# Power_Board_Schematic.net
KiCad netlist of a schematic drawn in Altium Designer
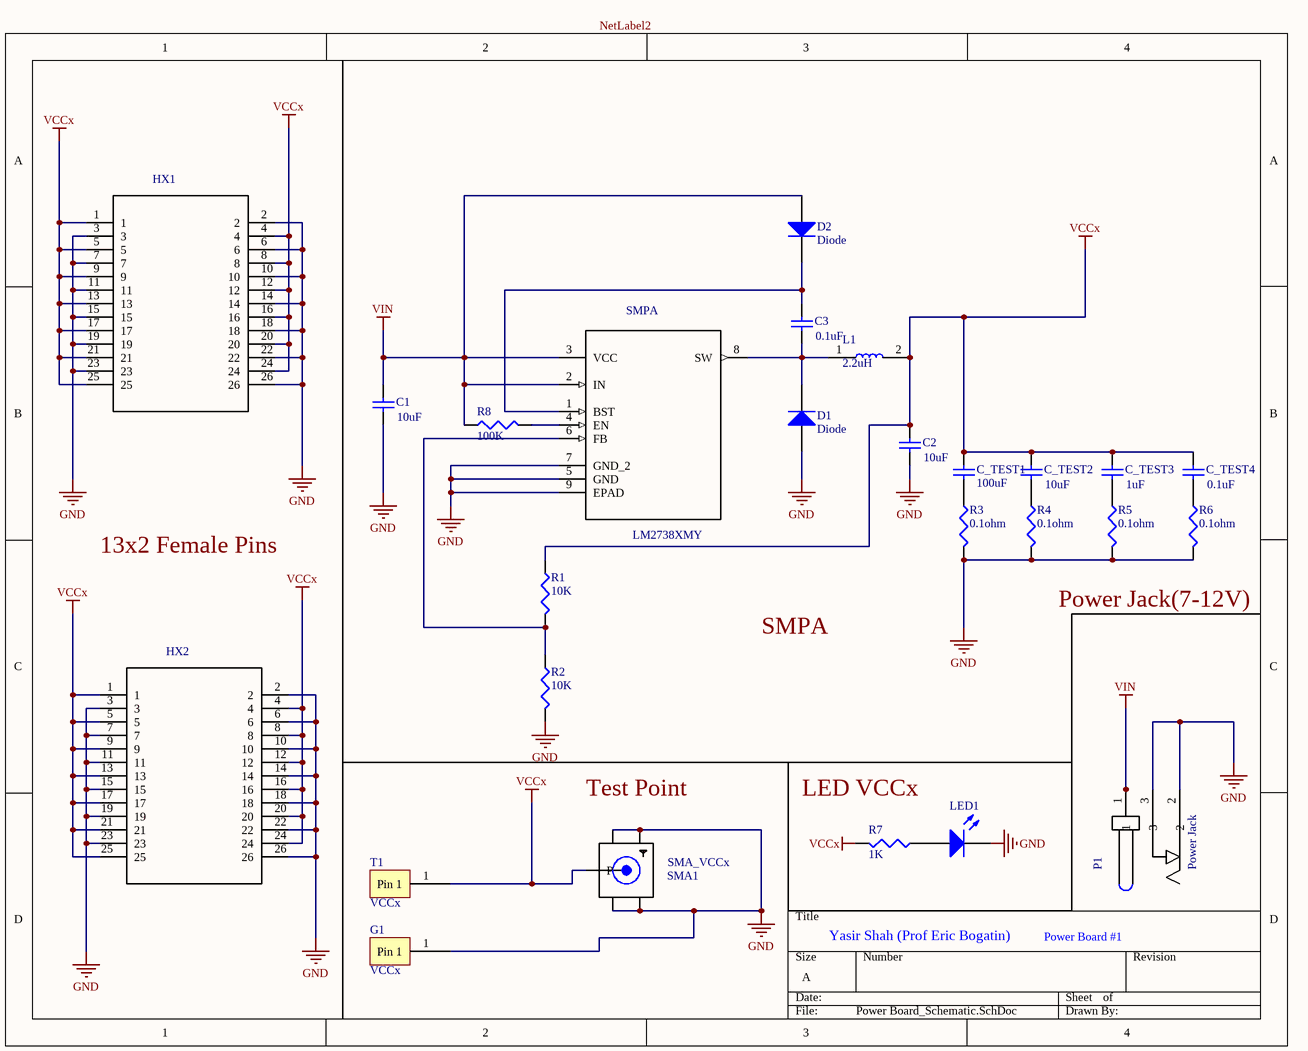
[diagram p0: Power Board_Schematic.SchDoc]

(export (version "E")
  (design (tool "Eeschema 10.0.6"))
  (components
    (comp (ref "C1")
      (value "10uF")
      (footprint "CAPC2012X140N")
      (description "Capacitor (Semiconductor SIM Model)")
      (fields (field (name "Comment") "Cap Semi") (field (name "PUBLISHER") "Altium Limited"))
      (libsource (lib "Miscellaneous Devices") (part "Cap Semi"))
    )
    (comp (ref "C2")
      (value "10uF")
      (footprint "CAPC2012X140N")
      (description "Capacitor (Semiconductor SIM Model)")
      (fields (field (name "Comment") "Cap Semi") (field (name "PUBLISHER") "Altium Limited"))
      (libsource (lib "Miscellaneous Devices") (part "Cap Semi"))
    )
    (comp (ref "C3")
      (value "0.1uF")
      (footprint "CAPC2012X140N")
      (description "Capacitor (Semiconductor SIM Model)")
      (fields (field (name "Comment") "Cap Semi") (field (name "PUBLISHER") "Altium Limited"))
      (libsource (lib "Miscellaneous Devices") (part "Cap Semi"))
    )
    (comp (ref "C_TEST1")
      (value "100uF")
      (footprint "CAPC2012X140N")
      (description "Capacitor (Semiconductor SIM Model)")
      (fields (field (name "Comment") "Cap Semi") (field (name "PUBLISHER") "Altium Limited"))
      (libsource (lib "Miscellaneous Devices") (part "Cap Semi"))
    )
    (comp (ref "C_TEST2")
      (value "10uF")
      (footprint "CAPC2012X140N")
      (description "Capacitor (Semiconductor SIM Model)")
      (fields (field (name "Comment") "Cap Semi") (field (name "PUBLISHER") "Altium Limited"))
      (libsource (lib "Miscellaneous Devices") (part "Cap Semi"))
    )
    (comp (ref "C_TEST3")
      (value "1uF")
      (footprint "CAPC2012X140N")
      (description "Capacitor (Semiconductor SIM Model)")
      (fields (field (name "Comment") "Cap Semi") (field (name "PUBLISHER") "Altium Limited"))
      (libsource (lib "Miscellaneous Devices") (part "Cap Semi"))
    )
    (comp (ref "C_TEST4")
      (value "0.1uF")
      (footprint "CAPC2012X140N")
      (description "Capacitor (Semiconductor SIM Model)")
      (fields (field (name "Comment") "Cap Semi") (field (name "PUBLISHER") "Altium Limited"))
      (libsource (lib "Miscellaneous Devices") (part "Cap Semi"))
    )
    (comp (ref "D1")
      (value "Diode")
      (footprint "D1")
      (description "Default Diode")
      (fields (field (name "PUBLISHER") "Altium Limited"))
      (libsource (lib "Miscellaneous Devices") (part "Diode"))
    )
    (comp (ref "D2")
      (value "Diode")
      (footprint "d2")
      (description "Default Diode")
      (fields (field (name "PUBLISHER") "Altium Limited"))
      (libsource (lib "Miscellaneous Devices") (part "Diode"))
    )
    (comp (ref "G1")
      (value "VCCx")
      (footprint "PCBComponent_1")
      (libsource (lib "SchematicLibrary") (part "1Pin Header"))
    )
    (comp (ref "HX1")
      (value "~")
      (footprint "TYCO_1761606-9")
      (description "Header, Pin, Idc, Amp-Latch, 26 Pos, Low Profile, Pcb, Vertical, Black")
      (fields (field (name "MF") "TE Connectivity") (field (name "MP") "1761606-9"))
      (libsource (lib "1761606-9") (part "1761606-9"))
    )
    (comp (ref "HX2")
      (value "~")
      (footprint "TYCO_1761606-9")
      (description "Header, Pin, Idc, Amp-Latch, 26 Pos, Low Profile, Pcb, Vertical, Black")
      (fields (field (name "MF") "TE Connectivity") (field (name "MP") "1761606-9"))
      (libsource (lib "1761606-9") (part "1761606-9"))
    )
    (comp (ref "L1")
      (value "2.2uH")
      (footprint "CAPC2012X140N")
      (description "Inductor Power Shielded Multi-Layer 2.2uH 20% 2MHz Ferrite 1A 195mOhm DCR 0805 Punched Paper T/R")
      (fields (field (name "MF") "TDK") (field (name "MP") "MLP2012H2R2MT0S1"))
      (libsource (lib "MLP2012H2R2MT0S1") (part "MLP2012H2R2MT0S1"))
    )
    (comp (ref "LED1")
      (value "LED2")
      (footprint "C1206")
      (description "Typical RED, GREEN, YELLOW, AMBER GaAs LED")
      (fields (field (name "PUBLISHER") "Altium Limited"))
      (libsource (lib "Miscellaneous Devices") (part "LED2"))
    )
    (comp (ref "P1")
      (value "Power Jack")
      (footprint "CUI_PJ-002AH-SMT-TR")
      (description "24 VDC 5 A Surface Mount Unshielded 2 Conductors 3 Contacts Male Power Jack")
      (fields (field (name "MF") "CUI") (field (name "MP") "PJ-002AH-SMT-TR"))
      (libsource (lib "PJ-002AH-SMT-TR") (part "PJ-002AH-SMT-TR"))
    )
    (comp (ref "R1")
      (value "10K")
      (footprint "RESC2012X70")
      (description "Resistor")
      (fields (field (name "Comment") "Res3") (field (name "PUBLISHER") "Altium Limited"))
      (libsource (lib "Miscellaneous Devices") (part "Res3"))
    )
    (comp (ref "R2")
      (value "10K")
      (footprint "RESC2012X70")
      (description "Resistor")
      (fields (field (name "Comment") "Res3") (field (name "PUBLISHER") "Altium Limited"))
      (libsource (lib "Miscellaneous Devices") (part "Res3"))
    )
    (comp (ref "R3")
      (value "0.1ohm")
      (footprint "RESC3216X65")
      (description "Resistor")
      (fields (field (name "PUBLISHER") "Altium Limited"))
      (libsource (lib "Miscellaneous Devices") (part "Res3"))
    )
    (comp (ref "R4")
      (value "0.1ohm")
      (footprint "RESC3216X65")
      (description "Resistor")
      (fields (field (name "PUBLISHER") "Altium Limited"))
      (libsource (lib "Miscellaneous Devices") (part "Res3"))
    )
    (comp (ref "R5")
      (value "0.1ohm")
      (footprint "RESC3216X65")
      (description "Resistor")
      (fields (field (name "PUBLISHER") "Altium Limited"))
      (libsource (lib "Miscellaneous Devices") (part "Res3"))
    )
    (comp (ref "R6")
      (value "0.1ohm")
      (footprint "RESC3216X65")
      (description "Resistor")
      (fields (field (name "PUBLISHER") "Altium Limited"))
      (libsource (lib "Miscellaneous Devices") (part "Res3"))
    )
    (comp (ref "R7")
      (value "1K")
      (footprint "RESC2012X70")
      (description "Resistor")
      (fields (field (name "Comment") "Res3") (field (name "PUBLISHER") "Altium Limited"))
      (libsource (lib "Miscellaneous Devices") (part "Res3"))
    )
    (comp (ref "R8")
      (value "100K")
      (footprint "RESC2012X70")
      (description "Resistor")
      (fields (field (name "Comment") "Res3") (field (name "PUBLISHER") "Altium Limited"))
      (libsource (lib "Miscellaneous Devices") (part "Res3"))
    )
    (comp (ref "SMA_VCCx")
      (value "SMA1")
      (footprint "ADAFRUIT_1865_1865(Primary)")
      (description "Edge-Launch SMA Connector for 1.6mm / 0.062 Thick PCBs")
      (fields (field (name "MP") "1865") (field (name "MF") "Keystone"))
      (libsource (lib "1865") (part "1865"))
    )
    (comp (ref "SMPA")
      (value "LM2738XMY")
      (footprint "SOP65P490X110-9N")
      (description "Swx Reg, Step d, Dc-Dc, 1.5a, 8soic")
      (fields (field (name "MF") "Texas Instruments"))
      (libsource (lib "LM2738XMY") (part "LM2738XMY"))
    )
    (comp (ref "T1")
      (value "VCCx")
      (footprint "PCBComponent_1")
      (libsource (lib "SchematicLibrary") (part "1Pin Header"))
    )
  )
  (nets
    (net (code "2") (name "GND") (class "Default")
      (node (ref "C1") (pin "1") (pinfunction "1_1") (pintype "passive"))
      (node (ref "C2") (pin "1") (pinfunction "1_1") (pintype "passive"))
      (node (ref "D1") (pin "1") (pinfunction "A_1") (pintype "passive"))
      (node (ref "G1") (pin "1") (pinfunction "Pin_1_1") (pintype "passive"))
      (node (ref "HX1") (pin "10") (pinfunction "10_10") (pintype "passive"))
      (node (ref "HX1") (pin "11") (pinfunction "11_11") (pintype "passive"))
      (node (ref "HX1") (pin "14") (pinfunction "14_14") (pintype "passive"))
      (node (ref "HX1") (pin "15") (pinfunction "15_15") (pintype "passive"))
      (node (ref "HX1") (pin "18") (pinfunction "18_18") (pintype "passive"))
      (node (ref "HX1") (pin "19") (pinfunction "19_19") (pintype "passive"))
      (node (ref "HX1") (pin "2") (pinfunction "2_2") (pintype "passive"))
      (node (ref "HX1") (pin "22") (pinfunction "22_22") (pintype "passive"))
      (node (ref "HX1") (pin "23") (pinfunction "23_23") (pintype "passive"))
      (node (ref "HX1") (pin "26") (pinfunction "26_26") (pintype "passive"))
      (node (ref "HX1") (pin "3") (pinfunction "3_3") (pintype "passive"))
      (node (ref "HX1") (pin "6") (pinfunction "6_6") (pintype "passive"))
      (node (ref "HX1") (pin "7") (pinfunction "7_7") (pintype "passive"))
      (node (ref "HX2") (pin "10") (pinfunction "10_10") (pintype "passive"))
      (node (ref "HX2") (pin "11") (pinfunction "11_11") (pintype "passive"))
      (node (ref "HX2") (pin "14") (pinfunction "14_14") (pintype "passive"))
      (node (ref "HX2") (pin "15") (pinfunction "15_15") (pintype "passive"))
      (node (ref "HX2") (pin "18") (pinfunction "18_18") (pintype "passive"))
      (node (ref "HX2") (pin "19") (pinfunction "19_19") (pintype "passive"))
      (node (ref "HX2") (pin "2") (pinfunction "2_2") (pintype "passive"))
      (node (ref "HX2") (pin "22") (pinfunction "22_22") (pintype "passive"))
      (node (ref "HX2") (pin "23") (pinfunction "23_23") (pintype "passive"))
      (node (ref "HX2") (pin "26") (pinfunction "26_26") (pintype "passive"))
      (node (ref "HX2") (pin "3") (pinfunction "3_3") (pintype "passive"))
      (node (ref "HX2") (pin "6") (pinfunction "6_6") (pintype "passive"))
      (node (ref "HX2") (pin "7") (pinfunction "7_7") (pintype "passive"))
      (node (ref "LED1") (pin "2") (pinfunction "K_2") (pintype "passive"))
      (node (ref "P1") (pin "2") (pinfunction "2_2") (pintype "passive"))
      (node (ref "P1") (pin "3") (pinfunction "3_3") (pintype "passive"))
      (node (ref "R2") (pin "2") (pinfunction "2_2") (pintype "passive"))
      (node (ref "R3") (pin "2") (pinfunction "2_2") (pintype "passive"))
      (node (ref "R4") (pin "2") (pinfunction "2_2") (pintype "passive"))
      (node (ref "R5") (pin "2") (pinfunction "2_2") (pintype "passive"))
      (node (ref "R6") (pin "2") (pinfunction "2_2") (pintype "passive"))
      (node (ref "SMA_VCCx") (pin "GND1") (pinfunction "GND1_GND1") (pintype "power_in"))
      (node (ref "SMA_VCCx") (pin "GND2") (pinfunction "GND2_GND2") (pintype "power_in"))
      (node (ref "SMA_VCCx") (pin "GND3") (pinfunction "GND3_GND3") (pintype "power_in"))
      (node (ref "SMA_VCCx") (pin "GND4") (pinfunction "GND4_GND4") (pintype "power_in"))
      (node (ref "SMPA") (pin "5") (pinfunction "GND_5") (pintype "passive"))
      (node (ref "SMPA") (pin "7") (pinfunction "GND_2_7") (pintype "passive"))
      (node (ref "SMPA") (pin "9") (pinfunction "EPAD_9") (pintype "passive"))
    )
    (net (code "3") (name "Net-(C_TEST1-Pad2)") (class "Default")
      (node (ref "C_TEST1") (pin "2") (pinfunction "2_2") (pintype "passive"))
      (node (ref "R3") (pin "1") (pinfunction "1_1") (pintype "passive"))
    )
    (net (code "4") (name "Net-(C_TEST2-Pad1)") (class "Default")
      (node (ref "C_TEST2") (pin "1") (pinfunction "1_1") (pintype "passive"))
      (node (ref "R4") (pin "1") (pinfunction "1_1") (pintype "passive"))
    )
    (net (code "5") (name "Net-(C_TEST3-Pad1)") (class "Default")
      (node (ref "C_TEST3") (pin "1") (pinfunction "1_1") (pintype "passive"))
      (node (ref "R5") (pin "1") (pinfunction "1_1") (pintype "passive"))
    )
    (net (code "6") (name "Net-(C_TEST4-Pad1)") (class "Default")
      (node (ref "C_TEST4") (pin "1") (pinfunction "1_1") (pintype "passive"))
      (node (ref "R6") (pin "1") (pinfunction "1_1") (pintype "passive"))
    )
    (net (code "7") (name "Net-(D1-K)") (class "Default")
      (node (ref "C3") (pin "1") (pinfunction "1_1") (pintype "passive"))
      (node (ref "D1") (pin "2") (pinfunction "K_2") (pintype "passive"))
      (node (ref "L1") (pin "1") (pinfunction "1_1") (pintype "passive"))
      (node (ref "SMPA") (pin "8") (pinfunction "SW_8") (pintype "output"))
    )
    (net (code "8") (name "Net-(D2-K)") (class "Default")
      (node (ref "C3") (pin "2") (pinfunction "2_2") (pintype "passive"))
      (node (ref "D2") (pin "2") (pinfunction "K_2") (pintype "passive"))
      (node (ref "SMPA") (pin "1") (pinfunction "BST_1") (pintype "input"))
    )
    (net (code "9") (name "Net-(LED1-A)") (class "Default")
      (node (ref "LED1") (pin "1") (pinfunction "A_1") (pintype "passive"))
      (node (ref "R7") (pin "1") (pinfunction "1_1") (pintype "passive"))
    )
    (net (code "10") (name "Net-(SMPA-EN)") (class "Default")
      (node (ref "R8") (pin "2") (pinfunction "2_2") (pintype "passive"))
      (node (ref "SMPA") (pin "4") (pinfunction "EN_4") (pintype "input"))
    )
    (net (code "11") (name "Net-(SMPA-FB)") (class "Default")
      (node (ref "R1") (pin "2") (pinfunction "2_2") (pintype "passive"))
      (node (ref "R2") (pin "1") (pinfunction "1_1") (pintype "passive"))
      (node (ref "SMPA") (pin "6") (pinfunction "FB_6") (pintype "input"))
    )
    (net (code "12") (name "VCCx") (class "Default")
      (node (ref "C2") (pin "2") (pinfunction "2_2") (pintype "passive"))
      (node (ref "C_TEST1") (pin "1") (pinfunction "1_1") (pintype "passive"))
      (node (ref "C_TEST2") (pin "2") (pinfunction "2_2") (pintype "passive"))
      (node (ref "C_TEST3") (pin "2") (pinfunction "2_2") (pintype "passive"))
      (node (ref "C_TEST4") (pin "2") (pinfunction "2_2") (pintype "passive"))
      (node (ref "HX1") (pin "1") (pinfunction "1_1") (pintype "passive"))
      (node (ref "HX1") (pin "12") (pinfunction "12_12") (pintype "passive"))
      (node (ref "HX1") (pin "13") (pinfunction "13_13") (pintype "passive"))
      (node (ref "HX1") (pin "16") (pinfunction "16_16") (pintype "passive"))
      (node (ref "HX1") (pin "17") (pinfunction "17_17") (pintype "passive"))
      (node (ref "HX1") (pin "20") (pinfunction "20_20") (pintype "passive"))
      (node (ref "HX1") (pin "21") (pinfunction "21_21") (pintype "passive"))
      (node (ref "HX1") (pin "24") (pinfunction "24_24") (pintype "passive"))
      (node (ref "HX1") (pin "25") (pinfunction "25_25") (pintype "passive"))
      (node (ref "HX1") (pin "4") (pinfunction "4_4") (pintype "passive"))
      (node (ref "HX1") (pin "5") (pinfunction "5_5") (pintype "passive"))
      (node (ref "HX1") (pin "8") (pinfunction "8_8") (pintype "passive"))
      (node (ref "HX1") (pin "9") (pinfunction "9_9") (pintype "passive"))
      (node (ref "HX2") (pin "1") (pinfunction "1_1") (pintype "passive"))
      (node (ref "HX2") (pin "12") (pinfunction "12_12") (pintype "passive"))
      (node (ref "HX2") (pin "13") (pinfunction "13_13") (pintype "passive"))
      (node (ref "HX2") (pin "16") (pinfunction "16_16") (pintype "passive"))
      (node (ref "HX2") (pin "17") (pinfunction "17_17") (pintype "passive"))
      (node (ref "HX2") (pin "20") (pinfunction "20_20") (pintype "passive"))
      (node (ref "HX2") (pin "21") (pinfunction "21_21") (pintype "passive"))
      (node (ref "HX2") (pin "24") (pinfunction "24_24") (pintype "passive"))
      (node (ref "HX2") (pin "25") (pinfunction "25_25") (pintype "passive"))
      (node (ref "HX2") (pin "4") (pinfunction "4_4") (pintype "passive"))
      (node (ref "HX2") (pin "5") (pinfunction "5_5") (pintype "passive"))
      (node (ref "HX2") (pin "8") (pinfunction "8_8") (pintype "passive"))
      (node (ref "HX2") (pin "9") (pinfunction "9_9") (pintype "passive"))
      (node (ref "L1") (pin "2") (pinfunction "2_2") (pintype "passive"))
      (node (ref "R1") (pin "1") (pinfunction "1_1") (pintype "passive"))
      (node (ref "R7") (pin "2") (pinfunction "2_2") (pintype "passive"))
      (node (ref "SMA_VCCx") (pin "P") (pinfunction "P_P") (pintype "bidirectional"))
      (node (ref "T1") (pin "1") (pinfunction "Pin_1_1") (pintype "passive"))
    )
    (net (code "13") (name "VIN") (class "Default")
      (node (ref "C1") (pin "2") (pinfunction "2_2") (pintype "passive"))
      (node (ref "D2") (pin "1") (pinfunction "A_1") (pintype "passive"))
      (node (ref "P1") (pin "1") (pinfunction "1_1") (pintype "passive"))
      (node (ref "R8") (pin "1") (pinfunction "1_1") (pintype "passive"))
      (node (ref "SMPA") (pin "2") (pinfunction "IN_2") (pintype "input"))
      (node (ref "SMPA") (pin "3") (pinfunction "VCC_3") (pintype "power_in"))
    )
  )
)
